# FrontEndCircuit.net
KiCad netlist of a schematic drawn in Altium Designer
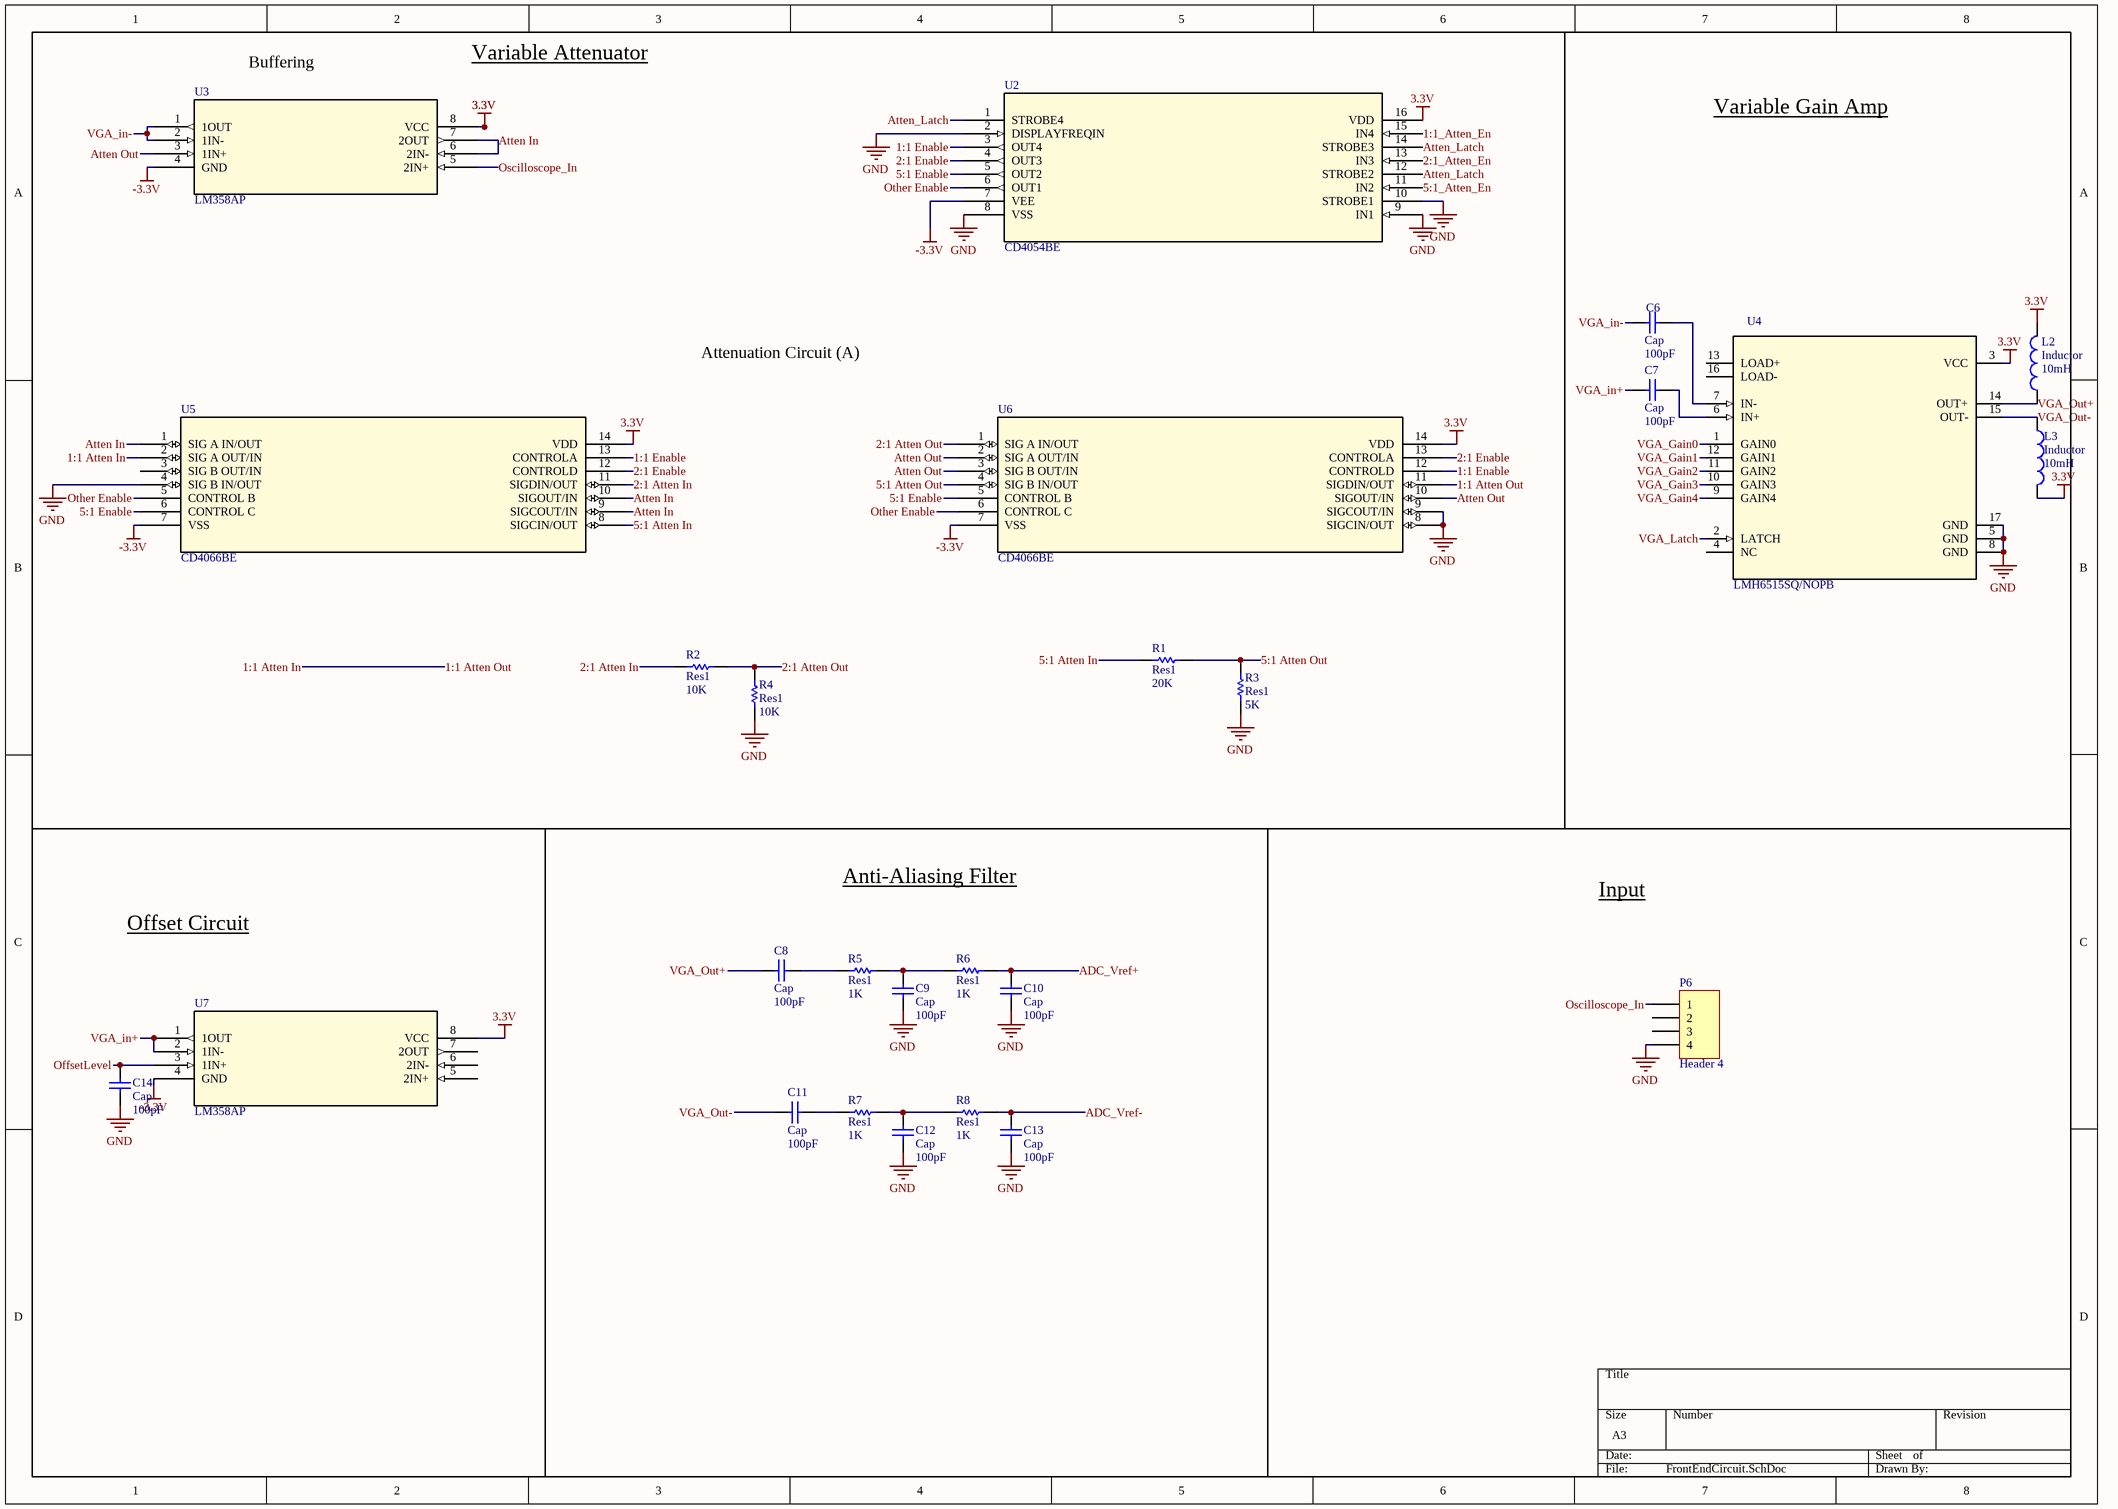
[diagram p0: FrontEndCircuit.SchDoc]

(export (version "E")
  (design (tool "Eeschema 10.0.6"))
  (components
    (comp (ref "C6")
      (value "Cap")
      (footprint "6-0805_N")
      (description "Capacitor")
      (fields (field (name "ALTIUM_VALUE") "100pF") (field (name "PUBLISHER") "Altium Limited"))
      (libsource (lib "Miscellaneous Devices") (part "Cap"))
    )
    (comp (ref "C7")
      (value "Cap")
      (footprint "6-0805_N")
      (description "Capacitor")
      (fields (field (name "ALTIUM_VALUE") "100pF") (field (name "PUBLISHER") "Altium Limited"))
      (libsource (lib "Miscellaneous Devices") (part "Cap"))
    )
    (comp (ref "C8")
      (value "Cap")
      (footprint "6-0805_N")
      (description "Capacitor")
      (fields (field (name "ALTIUM_VALUE") "100pF") (field (name "PUBLISHER") "Altium Limited"))
      (libsource (lib "Miscellaneous Devices") (part "Cap"))
    )
    (comp (ref "C9")
      (value "Cap")
      (footprint "6-0805_N")
      (description "Capacitor")
      (fields (field (name "ALTIUM_VALUE") "100pF") (field (name "PUBLISHER") "Altium Limited"))
      (libsource (lib "Miscellaneous Devices") (part "Cap"))
    )
    (comp (ref "C10")
      (value "Cap")
      (footprint "6-0805_N")
      (description "Capacitor")
      (fields (field (name "ALTIUM_VALUE") "100pF") (field (name "PUBLISHER") "Altium Limited"))
      (libsource (lib "Miscellaneous Devices") (part "Cap"))
    )
    (comp (ref "C11")
      (value "Cap")
      (footprint "6-0805_N")
      (description "Capacitor")
      (fields (field (name "ALTIUM_VALUE") "100pF") (field (name "PUBLISHER") "Altium Limited"))
      (libsource (lib "Miscellaneous Devices") (part "Cap"))
    )
    (comp (ref "C12")
      (value "Cap")
      (footprint "6-0805_N")
      (description "Capacitor")
      (fields (field (name "ALTIUM_VALUE") "100pF") (field (name "PUBLISHER") "Altium Limited"))
      (libsource (lib "Miscellaneous Devices") (part "Cap"))
    )
    (comp (ref "C13")
      (value "Cap")
      (footprint "6-0805_N")
      (description "Capacitor")
      (fields (field (name "ALTIUM_VALUE") "100pF") (field (name "PUBLISHER") "Altium Limited"))
      (libsource (lib "Miscellaneous Devices") (part "Cap"))
    )
    (comp (ref "C14")
      (value "Cap")
      (footprint "6-0805_N")
      (description "Capacitor")
      (fields (field (name "ALTIUM_VALUE") "100pF") (field (name "PUBLISHER") "Altium Limited"))
      (libsource (lib "Miscellaneous Devices") (part "Cap"))
    )
    (comp (ref "L2")
      (value "Inductor")
      (footprint "6-0805_N")
      (fields (field (name "ALTIUM_VALUE") "10mH") (field (name "PUBLISHER") "Altium Limited"))
      (libsource (lib "Miscellaneous Devices") (part "Inductor"))
    )
    (comp (ref "L3")
      (value "Inductor")
      (footprint "6-0805_N")
      (fields (field (name "ALTIUM_VALUE") "10mH") (field (name "PUBLISHER") "Altium Limited"))
      (libsource (lib "Miscellaneous Devices") (part "Inductor"))
    )
    (comp (ref "P6")
      (value "Header 4")
      (footprint "HDR1X4")
      (description "Header, 4-Pin")
      (fields (field (name "PUBLISHER") "Altium Limited"))
      (libsource (lib "Miscellaneous Connectors") (part "Header 4"))
    )
    (comp (ref "R1")
      (value "Res1")
      (footprint "AXIAL-0.3")
      (description "Resistor")
      (fields (field (name "ALTIUM_VALUE") "20K") (field (name "PUBLISHER") "Altium Limited"))
      (libsource (lib "Miscellaneous Devices") (part "Res1"))
    )
    (comp (ref "R2")
      (value "Res1")
      (footprint "AXIAL-0.3")
      (description "Resistor")
      (fields (field (name "ALTIUM_VALUE") "10K") (field (name "PUBLISHER") "Altium Limited"))
      (libsource (lib "Miscellaneous Devices") (part "Res1"))
    )
    (comp (ref "R3")
      (value "Res1")
      (footprint "AXIAL-0.3")
      (description "Resistor")
      (fields (field (name "ALTIUM_VALUE") "5K") (field (name "PUBLISHER") "Altium Limited"))
      (libsource (lib "Miscellaneous Devices") (part "Res1"))
    )
    (comp (ref "R4")
      (value "Res1")
      (footprint "AXIAL-0.3")
      (description "Resistor")
      (fields (field (name "ALTIUM_VALUE") "10K") (field (name "PUBLISHER") "Altium Limited"))
      (libsource (lib "Miscellaneous Devices") (part "Res1"))
    )
    (comp (ref "R5")
      (value "Res1")
      (footprint "AXIAL-0.3")
      (description "Resistor")
      (fields (field (name "ALTIUM_VALUE") "1K") (field (name "PUBLISHER") "Altium Limited"))
      (libsource (lib "Miscellaneous Devices") (part "Res1"))
    )
    (comp (ref "R6")
      (value "Res1")
      (footprint "AXIAL-0.3")
      (description "Resistor")
      (fields (field (name "ALTIUM_VALUE") "1K") (field (name "PUBLISHER") "Altium Limited"))
      (libsource (lib "Miscellaneous Devices") (part "Res1"))
    )
    (comp (ref "R7")
      (value "Res1")
      (footprint "AXIAL-0.3")
      (description "Resistor")
      (fields (field (name "ALTIUM_VALUE") "1K") (field (name "PUBLISHER") "Altium Limited"))
      (libsource (lib "Miscellaneous Devices") (part "Res1"))
    )
    (comp (ref "R8")
      (value "Res1")
      (footprint "AXIAL-0.3")
      (description "Resistor")
      (fields (field (name "ALTIUM_VALUE") "1K") (field (name "PUBLISHER") "Altium Limited"))
      (libsource (lib "Miscellaneous Devices") (part "Res1"))
    )
    (comp (ref "U2")
      (value "CD4054BE")
      (footprint "N16")
      (description "CMOS 4-Segment Liquid-Crystal Display Driver")
      (fields
        (field (name "MANUFACTURER") "Texas Instruments")
        (field (name "GENERIC_PART_NUMBER") "CD4054B")
        (field (name "COPYRIGHT") "Copyright (C) 2018 Accelerated Designs. All rights reserved")
      )
      (libsource (lib "CD4054BE") (part "CD4054BE"))
    )
    (comp (ref "U3")
      (value "LM358AP")
      (footprint "P8")
      (description "Dual Operational Amplifier")
      (fields
        (field (name "MANUFACTURER") "Texas Instruments")
        (field (name "GENERIC_PART_NUMBER") "LM358A")
        (field (name "COPYRIGHT") "Copyright (C) 2018 Accelerated Designs. All rights reserved")
      )
      (libsource (lib "LM358AP") (part "LM358AP"))
    )
    (comp (ref "U4")
      (value "LMH6515SQ/NOPB")
      (footprint "SQA16A")
      (description "No Description Available")
      (fields (field (name "COPYRIGHT") "Copyright (C) 2018 Accelerated Designs. All rights reserved"))
      (libsource (lib "LMH6515") (part "LMH6515SQ/NOPB"))
    )
    (comp (ref "U5")
      (value "CD4066BE")
      (footprint "N14")
      (description "CMOS Quad Bilateral Switch")
      (fields
        (field (name "MANUFACTURER") "Texas Instruments")
        (field (name "GENERIC_PART_NUMBER") "CD4066B")
        (field (name "COPYRIGHT") "Copyright (C) 2018 Accelerated Designs. All rights reserved")
      )
      (libsource (lib "CD4066BE") (part "CD4066BE"))
    )
    (comp (ref "U6")
      (value "CD4066BE")
      (footprint "N14")
      (description "CMOS Quad Bilateral Switch")
      (fields
        (field (name "MANUFACTURER") "Texas Instruments")
        (field (name "GENERIC_PART_NUMBER") "CD4066B")
        (field (name "COPYRIGHT") "Copyright (C) 2018 Accelerated Designs. All rights reserved")
      )
      (libsource (lib "CD4066BE") (part "CD4066BE"))
    )
    (comp (ref "U7")
      (value "LM358AP")
      (footprint "P8")
      (description "Dual Operational Amplifier")
      (fields
        (field (name "MANUFACTURER") "Texas Instruments")
        (field (name "GENERIC_PART_NUMBER") "LM358A")
        (field (name "COPYRIGHT") "Copyright (C) 2018 Accelerated Designs. All rights reserved")
      )
      (libsource (lib "LM358AP") (part "LM358AP"))
    )
  )
  (nets
    (net (code "1") (name "-3.3V") (class "Default")
      (node (ref "U2") (pin "7") (pinfunction "VEE_7") (pintype "power_in"))
      (node (ref "U3") (pin "4") (pinfunction "GND_4") (pintype "power_in"))
      (node (ref "U5") (pin "7") (pinfunction "VSS_7") (pintype "power_in"))
      (node (ref "U6") (pin "7") (pinfunction "VSS_7") (pintype "power_in"))
      (node (ref "U7") (pin "4") (pinfunction "GND_4") (pintype "power_in"))
    )
    (net (code "2") (name "/1:1 Atten In") (class "Default")
      (node (ref "U5") (pin "2") (pinfunction "SIG_A_OUT/IN_2") (pintype "bidirectional"))
      (node (ref "U6") (pin "11") (pinfunction "SIGDIN/OUT_11") (pintype "bidirectional"))
    )
    (net (code "3") (name "/1:1 Enable") (class "Default")
      (node (ref "U2") (pin "3") (pinfunction "OUT4_3") (pintype "output"))
      (node (ref "U5") (pin "13") (pinfunction "CONTROLA_13") (pintype "passive"))
      (node (ref "U6") (pin "12") (pinfunction "CONTROLD_12") (pintype "passive"))
    )
    (net (code "4") (name "/1:1_Atten_En") (class "Default")
      (node (ref "U2") (pin "15") (pinfunction "IN4_15") (pintype "input"))
    )
    (net (code "5") (name "/2:1 Atten In") (class "Default")
      (node (ref "R2") (pin "1") (pinfunction "1_1") (pintype "passive"))
      (node (ref "U5") (pin "11") (pinfunction "SIGDIN/OUT_11") (pintype "bidirectional"))
    )
    (net (code "6") (name "/2:1 Atten Out") (class "Default")
      (node (ref "R2") (pin "2") (pinfunction "2_2") (pintype "passive"))
      (node (ref "R4") (pin "2") (pinfunction "2_2") (pintype "passive"))
      (node (ref "U6") (pin "1") (pinfunction "SIG_A_IN/OUT_1") (pintype "bidirectional"))
    )
    (net (code "7") (name "/2:1 Enable") (class "Default")
      (node (ref "U2") (pin "4") (pinfunction "OUT3_4") (pintype "output"))
      (node (ref "U5") (pin "12") (pinfunction "CONTROLD_12") (pintype "passive"))
      (node (ref "U6") (pin "13") (pinfunction "CONTROLA_13") (pintype "passive"))
    )
    (net (code "8") (name "/2:1_Atten_En") (class "Default")
      (node (ref "U2") (pin "13") (pinfunction "IN3_13") (pintype "input"))
    )
    (net (code "9") (name "/5:1 Atten In") (class "Default")
      (node (ref "R1") (pin "1") (pinfunction "1_1") (pintype "passive"))
      (node (ref "U5") (pin "8") (pinfunction "SIGCIN/OUT_8") (pintype "bidirectional"))
    )
    (net (code "10") (name "/5:1 Atten Out") (class "Default")
      (node (ref "R1") (pin "2") (pinfunction "2_2") (pintype "passive"))
      (node (ref "R3") (pin "2") (pinfunction "2_2") (pintype "passive"))
      (node (ref "U6") (pin "4") (pinfunction "SIG_B_IN/OUT_4") (pintype "bidirectional"))
    )
    (net (code "11") (name "/5:1 Enable") (class "Default")
      (node (ref "U2") (pin "5") (pinfunction "OUT2_5") (pintype "output"))
      (node (ref "U5") (pin "6") (pinfunction "CONTROL_C_6") (pintype "passive"))
      (node (ref "U6") (pin "5") (pinfunction "CONTROL_B_5") (pintype "passive"))
    )
    (net (code "12") (name "/5:1_Atten_En") (class "Default")
      (node (ref "U2") (pin "11") (pinfunction "IN2_11") (pintype "input"))
    )
    (net (code "13") (name "/ADC_Vref+") (class "Default")
      (node (ref "C10") (pin "2") (pinfunction "2_2") (pintype "passive"))
      (node (ref "R6") (pin "2") (pinfunction "2_2") (pintype "passive"))
    )
    (net (code "14") (name "/ADC_Vref-") (class "Default")
      (node (ref "C13") (pin "2") (pinfunction "2_2") (pintype "passive"))
      (node (ref "R8") (pin "2") (pinfunction "2_2") (pintype "passive"))
    )
    (net (code "15") (name "/Atten In") (class "Default")
      (node (ref "U3") (pin "6") (pinfunction "2IN-_6") (pintype "input"))
      (node (ref "U3") (pin "7") (pinfunction "2OUT_7") (pintype "output"))
      (node (ref "U5") (pin "1") (pinfunction "SIG_A_IN/OUT_1") (pintype "bidirectional"))
      (node (ref "U5") (pin "10") (pinfunction "SIGOUT/IN_10") (pintype "bidirectional"))
      (node (ref "U5") (pin "9") (pinfunction "SIGCOUT/IN_9") (pintype "bidirectional"))
    )
    (net (code "16") (name "/Atten Out") (class "Default")
      (node (ref "U3") (pin "3") (pinfunction "1IN+_3") (pintype "input"))
      (node (ref "U6") (pin "10") (pinfunction "SIGOUT/IN_10") (pintype "bidirectional"))
      (node (ref "U6") (pin "2") (pinfunction "SIG_A_OUT/IN_2") (pintype "bidirectional"))
      (node (ref "U6") (pin "3") (pinfunction "SIG_B_OUT/IN_3") (pintype "bidirectional"))
    )
    (net (code "17") (name "/Atten_Latch") (class "Default")
      (node (ref "U2") (pin "1") (pinfunction "STROBE4_1") (pintype "passive"))
      (node (ref "U2") (pin "12") (pinfunction "STROBE2_12") (pintype "passive"))
      (node (ref "U2") (pin "14") (pinfunction "STROBE3_14") (pintype "passive"))
    )
    (net (code "18") (name "/OffsetLevel") (class "Default")
      (node (ref "C14") (pin "2") (pinfunction "2_2") (pintype "passive"))
      (node (ref "U7") (pin "3") (pinfunction "1IN+_3") (pintype "input"))
    )
    (net (code "19") (name "/Oscilloscope_In") (class "Default")
      (node (ref "P6") (pin "1") (pinfunction "1_1") (pintype "passive"))
      (node (ref "U3") (pin "5") (pinfunction "2IN+_5") (pintype "input"))
    )
    (net (code "20") (name "/Other Enable") (class "Default")
      (node (ref "U2") (pin "6") (pinfunction "OUT1_6") (pintype "output"))
      (node (ref "U5") (pin "5") (pinfunction "CONTROL_B_5") (pintype "passive"))
      (node (ref "U6") (pin "6") (pinfunction "CONTROL_C_6") (pintype "passive"))
    )
    (net (code "21") (name "/VGA_Gain0") (class "Default")
      (node (ref "U4") (pin "1") (pinfunction "GAIN0_1") (pintype "passive"))
    )
    (net (code "22") (name "/VGA_Gain1") (class "Default")
      (node (ref "U4") (pin "12") (pinfunction "GAIN1_12") (pintype "passive"))
    )
    (net (code "23") (name "/VGA_Gain2") (class "Default")
      (node (ref "U4") (pin "11") (pinfunction "GAIN2_11") (pintype "passive"))
    )
    (net (code "24") (name "/VGA_Gain3") (class "Default")
      (node (ref "U4") (pin "10") (pinfunction "GAIN3_10") (pintype "passive"))
    )
    (net (code "25") (name "/VGA_Gain4") (class "Default")
      (node (ref "U4") (pin "9") (pinfunction "GAIN4_9") (pintype "passive"))
    )
    (net (code "26") (name "/VGA_Latch") (class "Default")
      (node (ref "U4") (pin "2") (pinfunction "LATCH_2") (pintype "input"))
    )
    (net (code "27") (name "/VGA_Out+") (class "Default")
      (node (ref "C8") (pin "2") (pinfunction "2_2") (pintype "passive"))
      (node (ref "L2") (pin "1") (pinfunction "1_1") (pintype "passive"))
      (node (ref "U4") (pin "14") (pinfunction "OUT+_14") (pintype "passive"))
    )
    (net (code "28") (name "/VGA_Out-") (class "Default")
      (node (ref "C11") (pin "2") (pinfunction "2_2") (pintype "passive"))
      (node (ref "L3") (pin "1") (pinfunction "1_1") (pintype "passive"))
      (node (ref "U4") (pin "15") (pinfunction "OUT-_15") (pintype "passive"))
    )
    (net (code "29") (name "/VGA_in+") (class "Default")
      (node (ref "C7") (pin "1") (pinfunction "1_1") (pintype "passive"))
      (node (ref "U7") (pin "1") (pinfunction "1OUT_1") (pintype "output"))
      (node (ref "U7") (pin "2") (pinfunction "1IN-_2") (pintype "input"))
    )
    (net (code "30") (name "/VGA_in-") (class "Default")
      (node (ref "C6") (pin "1") (pinfunction "1_1") (pintype "passive"))
      (node (ref "U3") (pin "1") (pinfunction "1OUT_1") (pintype "output"))
      (node (ref "U3") (pin "2") (pinfunction "1IN-_2") (pintype "input"))
    )
    (net (code "31") (name "3.3V") (class "Default")
      (node (ref "L2") (pin "2") (pinfunction "2_2") (pintype "passive"))
      (node (ref "L3") (pin "2") (pinfunction "2_2") (pintype "passive"))
      (node (ref "U2") (pin "16") (pinfunction "VDD_16") (pintype "power_in"))
      (node (ref "U3") (pin "8") (pinfunction "VCC_8") (pintype "power_in"))
      (node (ref "U4") (pin "3") (pinfunction "VCC_3") (pintype "power_in"))
      (node (ref "U5") (pin "14") (pinfunction "VDD_14") (pintype "power_in"))
      (node (ref "U6") (pin "14") (pinfunction "VDD_14") (pintype "power_in"))
      (node (ref "U7") (pin "8") (pinfunction "VCC_8") (pintype "power_in"))
    )
    (net (code "32") (name "GND") (class "Default")
      (node (ref "C10") (pin "1") (pinfunction "1_1") (pintype "passive"))
      (node (ref "C12") (pin "1") (pinfunction "1_1") (pintype "passive"))
      (node (ref "C13") (pin "1") (pinfunction "1_1") (pintype "passive"))
      (node (ref "C14") (pin "1") (pinfunction "1_1") (pintype "passive"))
      (node (ref "C9") (pin "1") (pinfunction "1_1") (pintype "passive"))
      (node (ref "P6") (pin "4") (pinfunction "4_4") (pintype "passive"))
      (node (ref "R3") (pin "1") (pinfunction "1_1") (pintype "passive"))
      (node (ref "R4") (pin "1") (pinfunction "1_1") (pintype "passive"))
      (node (ref "U2") (pin "10") (pinfunction "STROBE1_10") (pintype "passive"))
      (node (ref "U2") (pin "2") (pinfunction "DISPLAYFREQIN_2") (pintype "input"))
      (node (ref "U2") (pin "8") (pinfunction "VSS_8") (pintype "power_in"))
      (node (ref "U2") (pin "9") (pinfunction "IN1_9") (pintype "input"))
      (node (ref "U4") (pin "17") (pinfunction "GND_17") (pintype "power_in"))
      (node (ref "U4") (pin "5") (pinfunction "GND_5") (pintype "power_in"))
      (node (ref "U4") (pin "8") (pinfunction "GND_8") (pintype "power_in"))
      (node (ref "U5") (pin "4") (pinfunction "SIG_B_IN/OUT_4") (pintype "bidirectional"))
      (node (ref "U6") (pin "8") (pinfunction "SIGCIN/OUT_8") (pintype "bidirectional"))
      (node (ref "U6") (pin "9") (pinfunction "SIGCOUT/IN_9") (pintype "bidirectional"))
    )
    (net (code "33") (name "Net-(C8-Pad1)") (class "Default")
      (node (ref "C8") (pin "1") (pinfunction "1_1") (pintype "passive"))
      (node (ref "R5") (pin "1") (pinfunction "1_1") (pintype "passive"))
    )
    (net (code "34") (name "Net-(C9-Pad2)") (class "Default")
      (node (ref "C9") (pin "2") (pinfunction "2_2") (pintype "passive"))
      (node (ref "R5") (pin "2") (pinfunction "2_2") (pintype "passive"))
      (node (ref "R6") (pin "1") (pinfunction "1_1") (pintype "passive"))
    )
    (net (code "35") (name "Net-(C11-Pad1)") (class "Default")
      (node (ref "C11") (pin "1") (pinfunction "1_1") (pintype "passive"))
      (node (ref "R7") (pin "1") (pinfunction "1_1") (pintype "passive"))
    )
    (net (code "36") (name "Net-(C12-Pad2)") (class "Default")
      (node (ref "C12") (pin "2") (pinfunction "2_2") (pintype "passive"))
      (node (ref "R7") (pin "2") (pinfunction "2_2") (pintype "passive"))
      (node (ref "R8") (pin "1") (pinfunction "1_1") (pintype "passive"))
    )
    (net (code "37") (name "Net-(U4-IN+)") (class "Default")
      (node (ref "C7") (pin "2") (pinfunction "2_2") (pintype "passive"))
      (node (ref "U4") (pin "6") (pinfunction "IN+_6") (pintype "input"))
    )
    (net (code "38") (name "Net-(U4-IN-)") (class "Default")
      (node (ref "C6") (pin "2") (pinfunction "2_2") (pintype "passive"))
      (node (ref "U4") (pin "7") (pinfunction "IN-_7") (pintype "input"))
    )
    (net (code "39") (name "unconnected-(P6-Pad2)") (class "Default")
      (node (ref "P6") (pin "2") (pinfunction "2_2") (pintype "passive"))
    )
    (net (code "40") (name "unconnected-(P6-Pad3)") (class "Default")
      (node (ref "P6") (pin "3") (pinfunction "3_3") (pintype "passive"))
    )
    (net (code "41") (name "unconnected-(U4-LOAD+-Pad13)") (class "Default")
      (node (ref "U4") (pin "13") (pinfunction "LOAD+_13") (pintype "passive"))
    )
    (net (code "42") (name "unconnected-(U4-LOAD--Pad16)") (class "Default")
      (node (ref "U4") (pin "16") (pinfunction "LOAD-_16") (pintype "passive"))
    )
    (net (code "43") (name "unconnected-(U4-NC-Pad4)") (class "Default")
      (node (ref "U4") (pin "4") (pinfunction "NC_4") (pintype "passive"))
    )
    (net (code "44") (name "unconnected-(U5-SIG_B_OUT{slash}IN-Pad3)") (class "Default")
      (node (ref "U5") (pin "3") (pinfunction "SIG_B_OUT/IN_3") (pintype "bidirectional"))
    )
    (net (code "45") (name "unconnected-(U7-2IN+-Pad5)") (class "Default")
      (node (ref "U7") (pin "5") (pinfunction "2IN+_5") (pintype "input"))
    )
    (net (code "46") (name "unconnected-(U7-2IN--Pad6)") (class "Default")
      (node (ref "U7") (pin "6") (pinfunction "2IN-_6") (pintype "input"))
    )
    (net (code "47") (name "unconnected-(U7-2OUT-Pad7)") (class "Default")
      (node (ref "U7") (pin "7") (pinfunction "2OUT_7") (pintype "output"))
    )
  )
)
